# SmartSwitch_V1_2.net
KiCad netlist of a schematic drawn in EAGLE
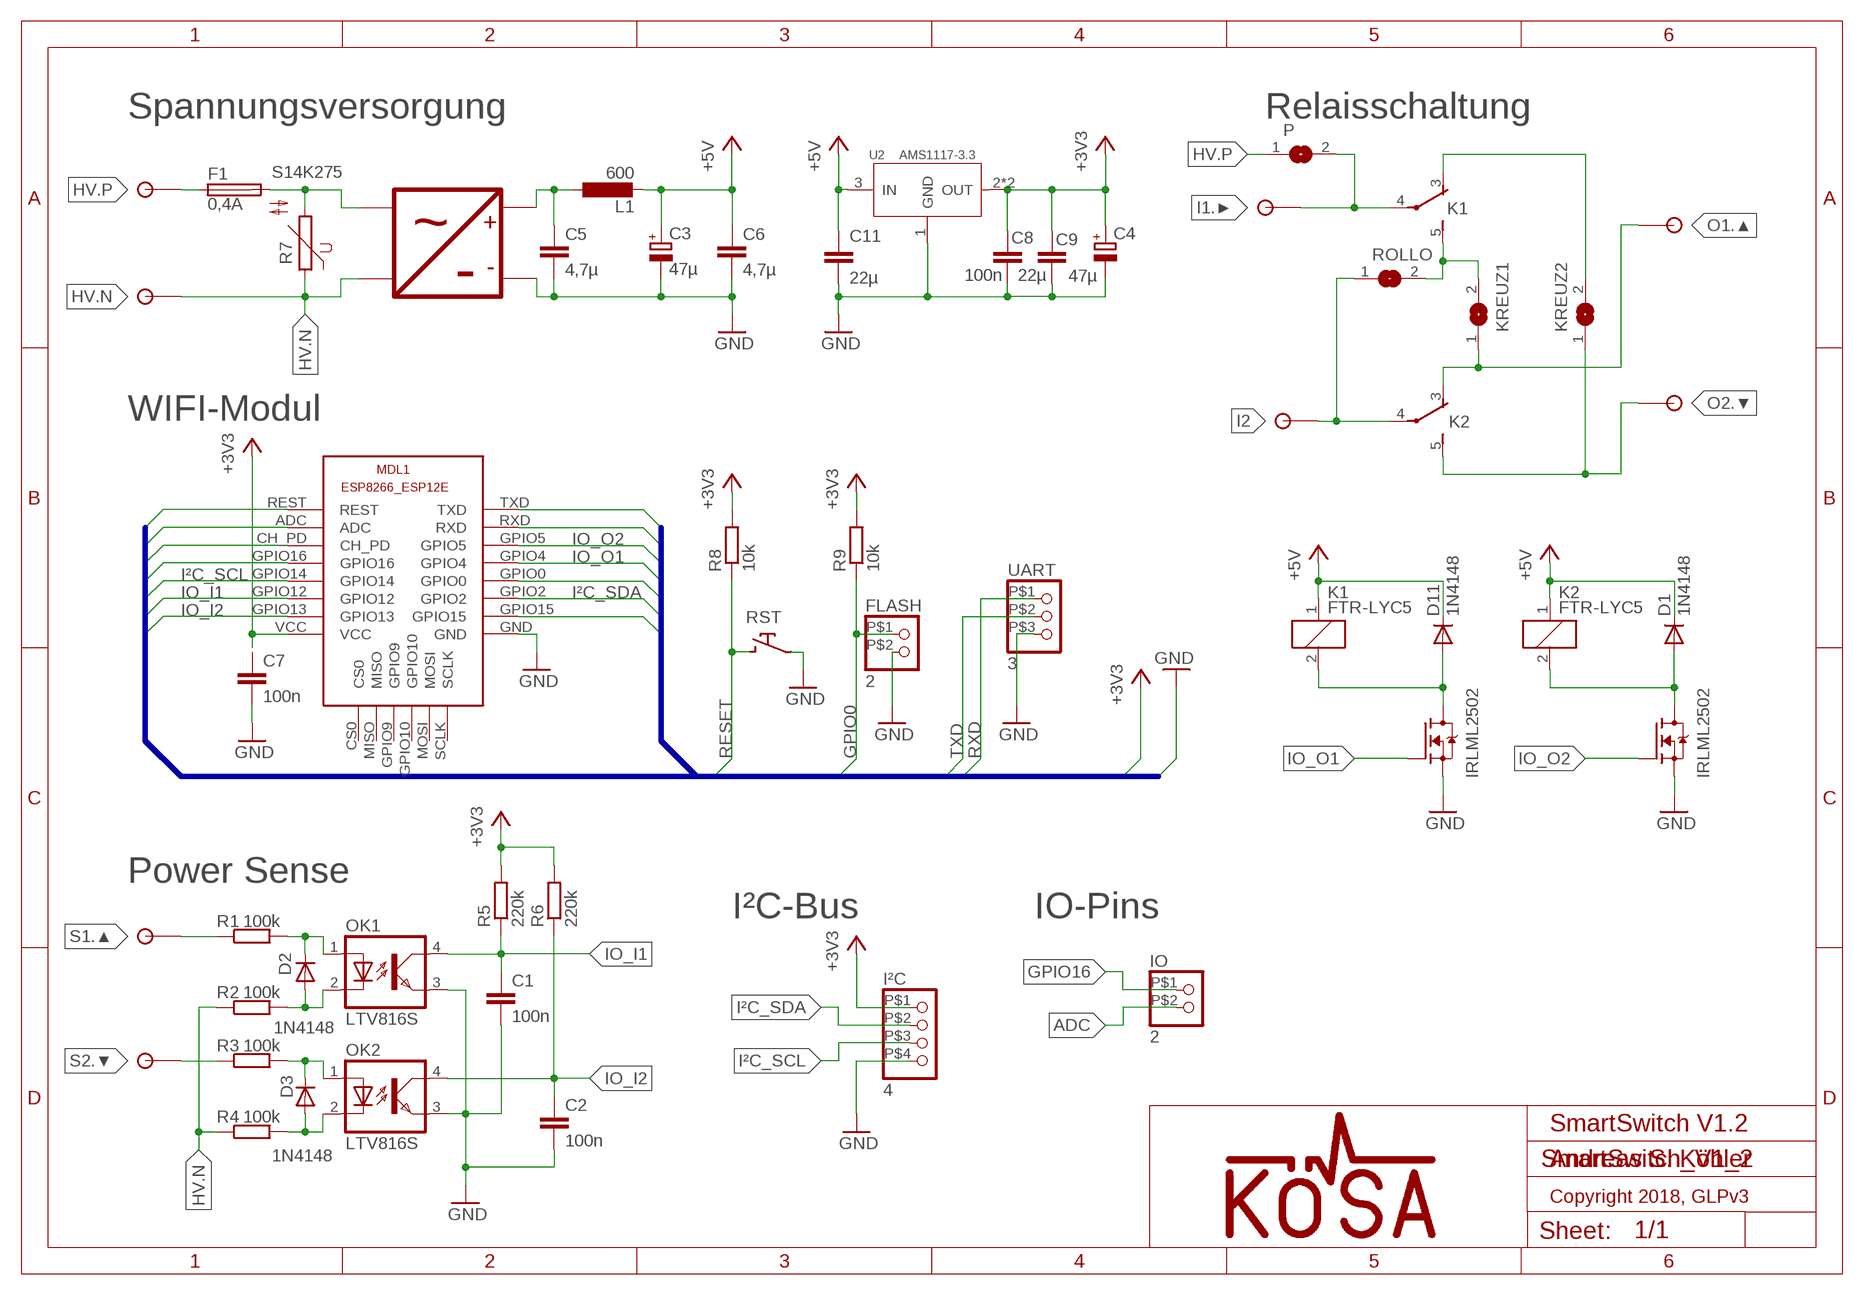
[diagram p0: schematic, sheet 1]

(export (version "E")
  (design (tool "Eeschema 10.0.6"))
  (components
    (comp (ref "C1")
      (value "100n")
      (footprint "eagle-import:C0805")
      (libsource (lib "eagle-import") (part "C-EUC0805"))
    )
    (comp (ref "C2")
      (value "100n")
      (footprint "eagle-import:C0805")
      (libsource (lib "eagle-import") (part "C-EUC0805"))
    )
    (comp (ref "C3")
      (value "47µ")
      (footprint "eagle-import:E2-5")
      (libsource (lib "eagle-import") (part "CPOL-EUE2-5"))
    )
    (comp (ref "C4")
      (value "47µ")
      (footprint "eagle-import:E2-5")
      (libsource (lib "eagle-import") (part "CPOL-EUE2-5"))
    )
    (comp (ref "C5")
      (value "4,7µ")
      (footprint "eagle-import:C0805")
      (libsource (lib "eagle-import") (part "C-EUC0805"))
    )
    (comp (ref "C6")
      (value "4,7µ")
      (footprint "eagle-import:C0805")
      (libsource (lib "eagle-import") (part "C-EUC0805"))
    )
    (comp (ref "C7")
      (value "100n")
      (footprint "eagle-import:C0805")
      (libsource (lib "eagle-import") (part "C-EUC0805"))
    )
    (comp (ref "C8")
      (value "100n")
      (footprint "eagle-import:C0805")
      (libsource (lib "eagle-import") (part "C-EUC0805"))
    )
    (comp (ref "C9")
      (value "22µ")
      (footprint "eagle-import:C0805")
      (libsource (lib "eagle-import") (part "C-EUC0805"))
    )
    (comp (ref "C11")
      (value "22µ")
      (footprint "eagle-import:C0805")
      (libsource (lib "eagle-import") (part "C-EUC0805"))
    )
    (comp (ref "D1")
      (value "1N4148")
      (footprint "eagle-import:SOD323-W")
      (libsource (lib "eagle-import") (part "DIODE-SOD323-W"))
    )
    (comp (ref "D2")
      (value "1N4148")
      (footprint "eagle-import:SOD323-W")
      (libsource (lib "eagle-import") (part "DIODE-SOD323-W"))
    )
    (comp (ref "D3")
      (value "1N4148")
      (footprint "eagle-import:SOD323-W")
      (libsource (lib "eagle-import") (part "DIODE-SOD323-W"))
    )
    (comp (ref "D11")
      (value "1N4148")
      (footprint "eagle-import:SOD323-W")
      (libsource (lib "eagle-import") (part "DIODE-SOD323-W"))
    )
    (comp (ref "F1")
      (value "0,4A")
      (footprint "eagle-import:SMD_FUSE_HOLDER")
      (libsource (lib "eagle-import") (part "SMD_FUSE_HOLDER"))
    )
    (comp (ref "FLASH")
      (value "2")
      (footprint "eagle-import:1X02_SMALL")
      (libsource (lib "eagle-import") (part "PINHD-1X2SMALL"))
    )
    (comp (ref "IO")
      (value "2")
      (footprint "eagle-import:1X02_SMALL")
      (libsource (lib "eagle-import") (part "PINHD-1X2SMALL"))
    )
    (comp (ref "I²C")
      (value "4")
      (footprint "eagle-import:1X04_SMALL")
      (libsource (lib "eagle-import") (part "PINHD-1X4SMALL"))
    )
    (comp (ref "K1")
      (value "FTR-LYC5")
      (footprint "eagle-import:FTR-LYC")
      (libsource (lib "eagle-import") (part "FTR-LYC5"))
    )
    (comp (ref "K2")
      (value "FTR-LYC5")
      (footprint "eagle-import:FTR-LYC")
      (libsource (lib "eagle-import") (part "FTR-LYC5"))
    )
    (comp (ref "KREUZ1")
      (value "SJW")
      (footprint "eagle-import:SJW")
      (libsource (lib "eagle-import") (part "SJW"))
    )
    (comp (ref "KREUZ2")
      (value "SJW")
      (footprint "eagle-import:SJW")
      (libsource (lib "eagle-import") (part "SJW"))
    )
    (comp (ref "L1")
      (value "600")
      (footprint "eagle-import:L3225P")
      (libsource (lib "eagle-import") (part "L-EUL3225P"))
    )
    (comp (ref "MDL1")
      (value "1")
      (footprint "eagle-import:ESP8266-ESP12E")
      (libsource (lib "eagle-import") (part "ESP8266-12EESP8266-ESP12E"))
    )
    (comp (ref "OK1")
      (value "LTV816S")
      (footprint "eagle-import:SMD4")
      (libsource (lib "eagle-import") (part "LTV816S"))
    )
    (comp (ref "OK2")
      (value "LTV816S")
      (footprint "eagle-import:SMD4")
      (libsource (lib "eagle-import") (part "LTV816S"))
    )
    (comp (ref "P")
      (value "SJW")
      (footprint "eagle-import:SJW")
      (libsource (lib "eagle-import") (part "SJW"))
    )
    (comp (ref "R1")
      (value "100k")
      (footprint "eagle-import:R1206")
      (libsource (lib "eagle-import") (part "R-EU_R1206"))
    )
    (comp (ref "R2")
      (value "100k")
      (footprint "eagle-import:R1206")
      (libsource (lib "eagle-import") (part "R-EU_R1206"))
    )
    (comp (ref "R3")
      (value "100k")
      (footprint "eagle-import:R1206")
      (libsource (lib "eagle-import") (part "R-EU_R1206"))
    )
    (comp (ref "R4")
      (value "100k")
      (footprint "eagle-import:R1206")
      (libsource (lib "eagle-import") (part "R-EU_R1206"))
    )
    (comp (ref "R5")
      (value "220k")
      (footprint "eagle-import:R1206")
      (libsource (lib "eagle-import") (part "R-EU_R1206"))
    )
    (comp (ref "R6")
      (value "220k")
      (footprint "eagle-import:R1206")
      (libsource (lib "eagle-import") (part "R-EU_R1206"))
    )
    (comp (ref "R7")
      (value "S14K275")
      (footprint "eagle-import:S14K275_")
      (libsource (lib "eagle-import") (part "S14K275GESPIEGELT"))
    )
    (comp (ref "R8")
      (value "10k")
      (footprint "eagle-import:R1206")
      (libsource (lib "eagle-import") (part "R-EU_R1206"))
    )
    (comp (ref "R9")
      (value "10k")
      (footprint "eagle-import:R1206")
      (libsource (lib "eagle-import") (part "R-EU_R1206"))
    )
    (comp (ref "ROLLO")
      (value "SJW")
      (footprint "eagle-import:SJW")
      (libsource (lib "eagle-import") (part "SJW"))
    )
    (comp (ref "RST")
      (value "SMD-TASTER_REICHELT_KMR_231_G_LFS")
      (footprint "eagle-import:SMD-TASTER_REICHELT_KMR_231_G_LFS")
      (libsource (lib "eagle-import") (part "SMD-TASTER_REICHELT_KMR_231_G_LFS"))
    )
    (comp (ref "U$1")
      (value "HLK-PM01")
      (footprint "eagle-import:HLK-PM01")
      (libsource (lib "eagle-import") (part "HLK-PM01"))
    )
    (comp (ref "U$2")
      (value "RND_205-00276")
      (footprint "eagle-import:RND205-00276")
      (libsource (lib "eagle-import") (part "RND_205-00276"))
    )
    (comp (ref "U$3")
      (value "RND_205-00276")
      (footprint "eagle-import:RND205-00276")
      (libsource (lib "eagle-import") (part "RND_205-00276"))
    )
    (comp (ref "U$4")
      (value "RND_205-00276")
      (footprint "eagle-import:RND205-00276")
      (libsource (lib "eagle-import") (part "RND_205-00276"))
    )
    (comp (ref "U$5")
      (value "RND_205-00276")
      (footprint "eagle-import:RND205-00276")
      (libsource (lib "eagle-import") (part "RND_205-00276"))
    )
    (comp (ref "U$7")
      (value "IRLML2502")
      (footprint "eagle-import:SOT23")
      (libsource (lib "eagle-import") (part "IRLML2502"))
    )
    (comp (ref "U$8")
      (value "IRLML2502")
      (footprint "eagle-import:SOT23")
      (libsource (lib "eagle-import") (part "IRLML2502"))
    )
    (comp (ref "U2")
      (value "AMS1117-3.3")
      (footprint "eagle-import:SOT-223")
      (fields (field (name "MPN") "CJT1117-3.3"))
      (libsource (lib "eagle-import") (part "PMIC-CJT1117-3.3(SOT223)"))
    )
    (comp (ref "UART")
      (value "3")
      (footprint "eagle-import:1X03_SMALL")
      (libsource (lib "eagle-import") (part "PINHD-1X3SMALL"))
    )
  )
  (nets
    (net (code "1") (name "+3V3") (class "Default")
      (node (ref "C4") (pin "+") (pinfunction "+_+") (pintype "passive"))
      (node (ref "C7") (pin "1") (pinfunction "1_1") (pintype "passive"))
      (node (ref "C8") (pin "1") (pinfunction "1_1") (pintype "passive"))
      (node (ref "C9") (pin "1") (pinfunction "1_1") (pintype "passive"))
      (node (ref "I²C") (pin "P$1") (pinfunction "1_P$1") (pintype "passive"))
      (node (ref "MDL1") (pin "CH_PD") (pinfunction "CH_PD_CH_PD") (pintype "bidirectional"))
      (node (ref "MDL1") (pin "VCC") (pinfunction "VCC_VCC") (pintype "bidirectional"))
      (node (ref "R5") (pin "2") (pinfunction "2_2") (pintype "passive"))
      (node (ref "R6") (pin "2") (pinfunction "2_2") (pintype "passive"))
      (node (ref "R8") (pin "2") (pinfunction "2_2") (pintype "passive"))
      (node (ref "R9") (pin "2") (pinfunction "2_2") (pintype "passive"))
      (node (ref "U2") (pin "2") (pinfunction "OUT_2") (pintype "bidirectional"))
      (node (ref "U2") (pin "TER") (pinfunction "OUT_TER") (pintype "bidirectional"))
    )
    (net (code "2") (name "+5V") (class "Default")
      (node (ref "C11") (pin "1") (pinfunction "1_1") (pintype "passive"))
      (node (ref "C3") (pin "+") (pinfunction "+_+") (pintype "passive"))
      (node (ref "C6") (pin "1") (pinfunction "1_1") (pintype "passive"))
      (node (ref "D1") (pin "C") (pinfunction "C_C") (pintype "passive"))
      (node (ref "D11") (pin "C") (pinfunction "C_C") (pintype "passive"))
      (node (ref "K1") (pin "1") (pinfunction "1_1") (pintype "passive"))
      (node (ref "K2") (pin "1") (pinfunction "1_1") (pintype "passive"))
      (node (ref "L1") (pin "2") (pinfunction "2_2") (pintype "passive"))
      (node (ref "U2") (pin "3") (pinfunction "IN_3") (pintype "bidirectional"))
    )
    (net (code "3") (name "/GPIO0") (class "Default")
      (node (ref "FLASH") (pin "P$1") (pinfunction "1_P$1") (pintype "passive"))
      (node (ref "MDL1") (pin "GPIO0") (pinfunction "GPIO0_GPIO0") (pintype "bidirectional"))
      (node (ref "R9") (pin "1") (pinfunction "1_1") (pintype "passive"))
    )
    (net (code "4") (name "/RESET") (class "Default")
      (node (ref "MDL1") (pin "REST") (pinfunction "REST_REST") (pintype "bidirectional"))
      (node (ref "R8") (pin "1") (pinfunction "1_1") (pintype "passive"))
      (node (ref "RST") (pin "2_1") (pinfunction "B_2_1") (pintype "bidirectional"))
      (node (ref "RST") (pin "2_2") (pinfunction "B_2_2") (pintype "bidirectional"))
    )
    (net (code "5") (name "/RXD") (class "Default")
      (node (ref "MDL1") (pin "RXD") (pinfunction "RXD_RXD") (pintype "bidirectional"))
      (node (ref "UART") (pin "P$1") (pinfunction "1_P$1") (pintype "passive"))
    )
    (net (code "6") (name "/TXD") (class "Default")
      (node (ref "MDL1") (pin "TXD") (pinfunction "TXD_TXD") (pintype "bidirectional"))
      (node (ref "UART") (pin "P$2") (pinfunction "2_P$2") (pintype "passive"))
    )
    (net (code "7") (name "ADC") (class "Default")
      (node (ref "IO") (pin "P$2") (pinfunction "2_P$2") (pintype "passive"))
      (node (ref "MDL1") (pin "ADC") (pinfunction "ADC_ADC") (pintype "bidirectional"))
    )
    (net (code "8") (name "GND") (class "Default")
      (node (ref "C1") (pin "2") (pinfunction "2_2") (pintype "passive"))
      (node (ref "C11") (pin "2") (pinfunction "2_2") (pintype "passive"))
      (node (ref "C2") (pin "2") (pinfunction "2_2") (pintype "passive"))
      (node (ref "C3") (pin "-") (pinfunction "-_-") (pintype "passive"))
      (node (ref "C4") (pin "-") (pinfunction "-_-") (pintype "passive"))
      (node (ref "C5") (pin "2") (pinfunction "2_2") (pintype "passive"))
      (node (ref "C6") (pin "2") (pinfunction "2_2") (pintype "passive"))
      (node (ref "C7") (pin "2") (pinfunction "2_2") (pintype "passive"))
      (node (ref "C8") (pin "2") (pinfunction "2_2") (pintype "passive"))
      (node (ref "C9") (pin "2") (pinfunction "2_2") (pintype "passive"))
      (node (ref "FLASH") (pin "P$2") (pinfunction "2_P$2") (pintype "passive"))
      (node (ref "I²C") (pin "P$4") (pinfunction "4_P$4") (pintype "passive"))
      (node (ref "MDL1") (pin "GND") (pinfunction "GND_GND") (pintype "bidirectional"))
      (node (ref "MDL1") (pin "GPIO15") (pinfunction "GPIO15_GPIO15") (pintype "bidirectional"))
      (node (ref "OK1") (pin "3") (pinfunction "EMIT_3") (pintype "passive"))
      (node (ref "OK2") (pin "3") (pinfunction "EMIT_3") (pintype "passive"))
      (node (ref "RST") (pin "1_1") (pinfunction "A_1_1") (pintype "bidirectional"))
      (node (ref "RST") (pin "1_2") (pinfunction "A_1_2") (pintype "bidirectional"))
      (node (ref "U$1") (pin "DC-") (pinfunction "DC-_DC-") (pintype "power_in"))
      (node (ref "U$7") (pin "2") (pinfunction "S_2") (pintype "passive"))
      (node (ref "U$8") (pin "2") (pinfunction "S_2") (pintype "passive"))
      (node (ref "U2") (pin "1") (pinfunction "GND_1") (pintype "bidirectional"))
      (node (ref "UART") (pin "P$3") (pinfunction "3_P$3") (pintype "passive"))
    )
    (net (code "9") (name "GPIO16") (class "Default")
      (node (ref "IO") (pin "P$1") (pinfunction "1_P$1") (pintype "passive"))
      (node (ref "MDL1") (pin "GPIO16") (pinfunction "GPIO16_GPIO16") (pintype "bidirectional"))
    )
    (net (code "10") (name "HV.N") (class "Default")
      (node (ref "R2") (pin "1") (pinfunction "1_1") (pintype "passive"))
      (node (ref "R4") (pin "1") (pinfunction "1_1") (pintype "passive"))
      (node (ref "R7") (pin "1") (pinfunction "1_1") (pintype "passive"))
      (node (ref "U$1") (pin "AC2") (pinfunction "AC2_AC2") (pintype "power_in"))
      (node (ref "U$2") (pin "P$2") (pinfunction "P$1_P$2") (pintype "bidirectional"))
    )
    (net (code "11") (name "HV.P") (class "Default")
      (node (ref "F1") (pin "P$1") (pinfunction "1_P$1") (pintype "passive"))
      (node (ref "P") (pin "1") (pinfunction "1_1") (pintype "passive"))
      (node (ref "U$2") (pin "P$1") (pinfunction "P$1_P$1") (pintype "bidirectional"))
    )
    (net (code "12") (name "I1.►") (class "Default")
      (node (ref "K1") (pin "4") (pinfunction "P_4") (pintype "passive"))
      (node (ref "P") (pin "2") (pinfunction "2_2") (pintype "passive"))
      (node (ref "U$4") (pin "P$1") (pinfunction "P$1_P$1") (pintype "bidirectional"))
    )
    (net (code "13") (name "I2") (class "Default")
      (node (ref "K2") (pin "4") (pinfunction "P_4") (pintype "passive"))
      (node (ref "ROLLO") (pin "1") (pinfunction "1_1") (pintype "passive"))
      (node (ref "U$3") (pin "P$1") (pinfunction "P$1_P$1") (pintype "bidirectional"))
    )
    (net (code "14") (name "IO_I1") (class "Default")
      (node (ref "C1") (pin "1") (pinfunction "1_1") (pintype "passive"))
      (node (ref "MDL1") (pin "GPIO12") (pinfunction "GPIO12_GPIO12") (pintype "bidirectional"))
      (node (ref "OK1") (pin "4") (pinfunction "COL_4") (pintype "passive"))
      (node (ref "R5") (pin "1") (pinfunction "1_1") (pintype "passive"))
    )
    (net (code "15") (name "IO_I2") (class "Default")
      (node (ref "C2") (pin "1") (pinfunction "1_1") (pintype "passive"))
      (node (ref "MDL1") (pin "GPIO13") (pinfunction "GPIO13_GPIO13") (pintype "bidirectional"))
      (node (ref "OK2") (pin "4") (pinfunction "COL_4") (pintype "passive"))
      (node (ref "R6") (pin "1") (pinfunction "1_1") (pintype "passive"))
    )
    (net (code "16") (name "IO_O1") (class "Default")
      (node (ref "MDL1") (pin "GPIO4") (pinfunction "GPIO4_GPIO4") (pintype "bidirectional"))
      (node (ref "U$7") (pin "1") (pinfunction "G_1") (pintype "passive"))
    )
    (net (code "17") (name "IO_O2") (class "Default")
      (node (ref "MDL1") (pin "GPIO5") (pinfunction "GPIO5_GPIO5") (pintype "bidirectional"))
      (node (ref "U$8") (pin "1") (pinfunction "G_1") (pintype "passive"))
    )
    (net (code "18") (name "I²C_SCL") (class "Default")
      (node (ref "I²C") (pin "P$3") (pinfunction "3_P$3") (pintype "passive"))
      (node (ref "MDL1") (pin "GPIO14") (pinfunction "GPIO14_GPIO14") (pintype "bidirectional"))
    )
    (net (code "19") (name "I²C_SDA") (class "Default")
      (node (ref "I²C") (pin "P$2") (pinfunction "2_P$2") (pintype "passive"))
      (node (ref "MDL1") (pin "GPIO2") (pinfunction "GPIO2_GPIO2") (pintype "bidirectional"))
    )
    (net (code "20") (name "Net-(C5-Pad1)") (class "Default")
      (node (ref "C5") (pin "1") (pinfunction "1_1") (pintype "passive"))
      (node (ref "L1") (pin "1") (pinfunction "1_1") (pintype "passive"))
      (node (ref "U$1") (pin "DC+") (pinfunction "DC+_DC+") (pintype "power_in"))
    )
    (net (code "21") (name "Net-(F1-2)") (class "Default")
      (node (ref "F1") (pin "P$2") (pinfunction "2_P$2") (pintype "passive"))
      (node (ref "R7") (pin "2") (pinfunction "2_2") (pintype "passive"))
      (node (ref "U$1") (pin "AC1") (pinfunction "AC1_AC1") (pintype "power_in"))
    )
    (net (code "22") (name "Net-(K1A-O)") (class "Default")
      (node (ref "K1") (pin "3") (pinfunction "O_3") (pintype "passive"))
      (node (ref "KREUZ2") (pin "2") (pinfunction "2_2") (pintype "passive"))
    )
    (net (code "23") (name "Net-(K1A-S)") (class "Default")
      (node (ref "K1") (pin "5") (pinfunction "S_5") (pintype "passive"))
      (node (ref "KREUZ1") (pin "2") (pinfunction "2_2") (pintype "passive"))
      (node (ref "ROLLO") (pin "2") (pinfunction "2_2") (pintype "passive"))
    )
    (net (code "24") (name "Net-(OK1-A)") (class "Default")
      (node (ref "D2") (pin "C") (pinfunction "C_C") (pintype "passive"))
      (node (ref "OK1") (pin "1") (pinfunction "A_1") (pintype "passive"))
      (node (ref "R1") (pin "2") (pinfunction "2_2") (pintype "passive"))
    )
    (net (code "25") (name "Net-(OK1-C)") (class "Default")
      (node (ref "D2") (pin "A") (pinfunction "A_A") (pintype "passive"))
      (node (ref "OK1") (pin "2") (pinfunction "C_2") (pintype "passive"))
      (node (ref "R2") (pin "2") (pinfunction "2_2") (pintype "passive"))
    )
    (net (code "26") (name "Net-(OK2-A)") (class "Default")
      (node (ref "D3") (pin "C") (pinfunction "C_C") (pintype "passive"))
      (node (ref "OK2") (pin "1") (pinfunction "A_1") (pintype "passive"))
      (node (ref "R3") (pin "2") (pinfunction "2_2") (pintype "passive"))
    )
    (net (code "27") (name "Net-(OK2-C)") (class "Default")
      (node (ref "D3") (pin "A") (pinfunction "A_A") (pintype "passive"))
      (node (ref "OK2") (pin "2") (pinfunction "C_2") (pintype "passive"))
      (node (ref "R4") (pin "2") (pinfunction "2_2") (pintype "passive"))
    )
    (net (code "28") (name "Net-(U$7-D)") (class "Default")
      (node (ref "D11") (pin "A") (pinfunction "A_A") (pintype "passive"))
      (node (ref "K1") (pin "2") (pinfunction "2_2") (pintype "passive"))
      (node (ref "U$7") (pin "3") (pinfunction "D_3") (pintype "passive"))
    )
    (net (code "29") (name "Net-(U$8-D)") (class "Default")
      (node (ref "D1") (pin "A") (pinfunction "A_A") (pintype "passive"))
      (node (ref "K2") (pin "2") (pinfunction "2_2") (pintype "passive"))
      (node (ref "U$8") (pin "3") (pinfunction "D_3") (pintype "passive"))
    )
    (net (code "30") (name "O1.▲") (class "Default")
      (node (ref "K2") (pin "3") (pinfunction "O_3") (pintype "passive"))
      (node (ref "KREUZ1") (pin "1") (pinfunction "1_1") (pintype "passive"))
      (node (ref "U$3") (pin "P$2") (pinfunction "P$1_P$2") (pintype "bidirectional"))
    )
    (net (code "31") (name "O2.▼") (class "Default")
      (node (ref "K2") (pin "5") (pinfunction "S_5") (pintype "passive"))
      (node (ref "KREUZ2") (pin "1") (pinfunction "1_1") (pintype "passive"))
      (node (ref "U$4") (pin "P$2") (pinfunction "P$1_P$2") (pintype "bidirectional"))
    )
    (net (code "32") (name "S1.▲") (class "Default")
      (node (ref "R1") (pin "1") (pinfunction "1_1") (pintype "passive"))
      (node (ref "U$5") (pin "P$2") (pinfunction "P$1_P$2") (pintype "bidirectional"))
    )
    (net (code "33") (name "S2.▼") (class "Default")
      (node (ref "R3") (pin "1") (pinfunction "1_1") (pintype "passive"))
      (node (ref "U$5") (pin "P$1") (pinfunction "P$1_P$1") (pintype "bidirectional"))
    )
    (net (code "34") (name "unconnected-(MDL1-PadCS0)") (class "Default")
      (node (ref "MDL1") (pin "CS0") (pinfunction "CS0_CS0") (pintype "bidirectional"))
    )
    (net (code "35") (name "unconnected-(MDL1-PadGPIO9)") (class "Default")
      (node (ref "MDL1") (pin "GPIO9") (pinfunction "GPIO9_GPIO9") (pintype "bidirectional"))
    )
    (net (code "36") (name "unconnected-(MDL1-PadGPIO10)") (class "Default")
      (node (ref "MDL1") (pin "GPIO10") (pinfunction "GPIO10_GPIO10") (pintype "bidirectional"))
    )
    (net (code "37") (name "unconnected-(MDL1-PadMISO)") (class "Default")
      (node (ref "MDL1") (pin "MISO") (pinfunction "MISO_MISO") (pintype "bidirectional"))
    )
    (net (code "38") (name "unconnected-(MDL1-PadMOSI)") (class "Default")
      (node (ref "MDL1") (pin "MOSI") (pinfunction "MOSI_MOSI") (pintype "bidirectional"))
    )
    (net (code "39") (name "unconnected-(MDL1-PadSCLK)") (class "Default")
      (node (ref "MDL1") (pin "SCLK") (pinfunction "SCLK_SCLK") (pintype "bidirectional"))
    )
  )
)
